# shadower.net
KiCad netlist of a schematic drawn in EAGLE
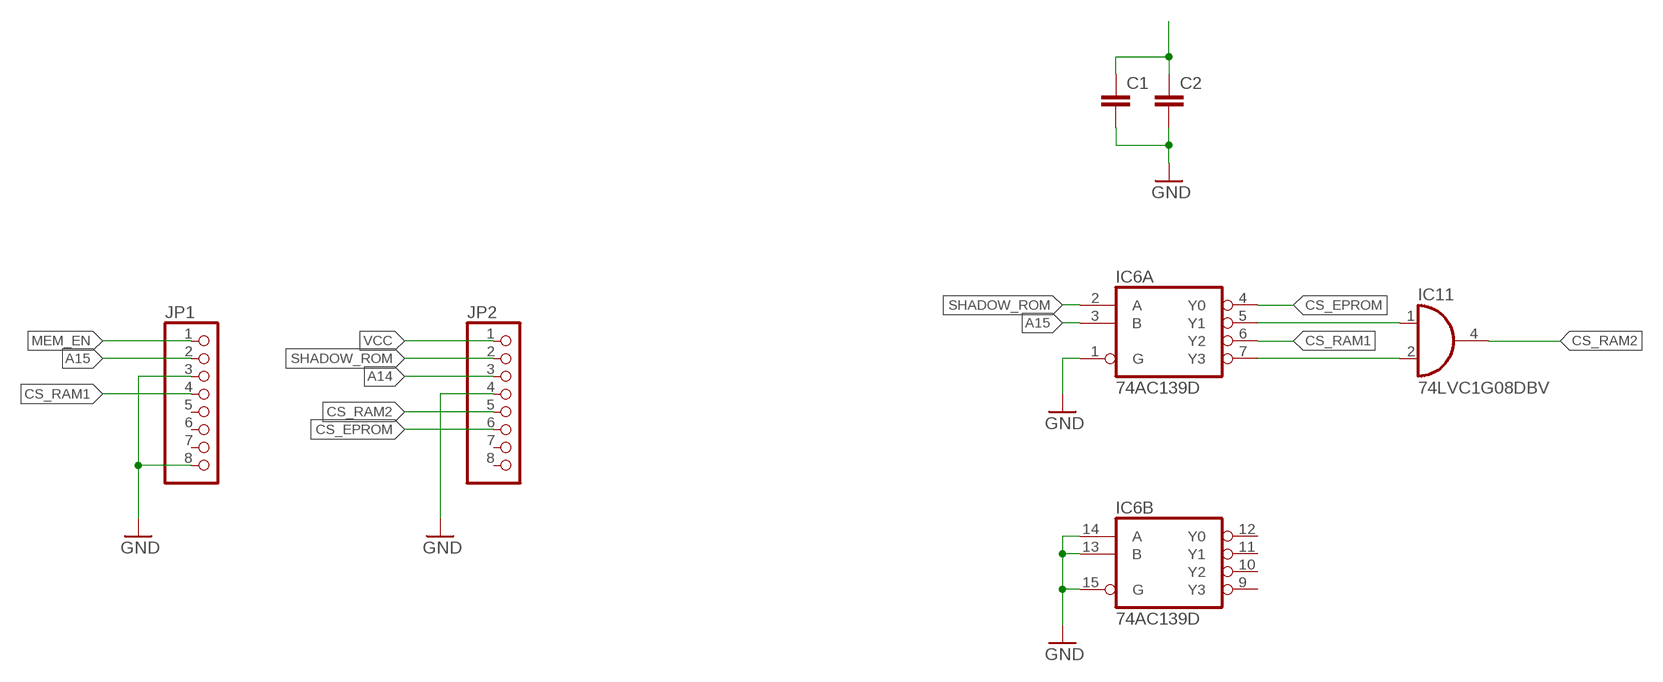
[diagram p0: schematic, sheet 1]

(export (version "E")
  (design (tool "Eeschema 10.0.6"))
  (components
    (comp (ref "C1")
      (value "C-EUC0603")
      (footprint "eagle-import:C0603")
      (libsource (lib "eagle-import") (part "C-EUC0603"))
    )
    (comp (ref "C2")
      (value "C-EUC0603")
      (footprint "eagle-import:C0603")
      (libsource (lib "eagle-import") (part "C-EUC0603"))
    )
    (comp (ref "IC6")
      (value "74AC139D")
      (footprint "eagle-import:SO16")
      (libsource (lib "eagle-import") (part "74139DAC"))
    )
    (comp (ref "IC11")
      (value "74LVC1G08DBV")
      (footprint "eagle-import:SOT23-5")
      (libsource (lib "eagle-import") (part "741G08DBVLVC"))
    )
    (comp (ref "JP1")
      (value "PINHD-1X8")
      (footprint "eagle-import:1X08")
      (libsource (lib "eagle-import") (part "PINHD-1X8"))
    )
    (comp (ref "JP2")
      (value "PINHD-1X8")
      (footprint "eagle-import:1X08")
      (libsource (lib "eagle-import") (part "PINHD-1X8"))
    )
  )
  (nets
    (net (code "1") (name "A14") (class "Default")
      (node (ref "JP2") (pin "3") (pinfunction "3_3") (pintype "passive"))
    )
    (net (code "2") (name "A15") (class "Default")
      (node (ref "IC6") (pin "3") (pinfunction "B_3") (pintype "input"))
      (node (ref "JP1") (pin "2") (pinfunction "2_2") (pintype "passive"))
    )
    (net (code "3") (name "CS_EPROM") (class "Default")
      (node (ref "IC6") (pin "4") (pinfunction "Y0_4") (pintype "output"))
      (node (ref "JP2") (pin "6") (pinfunction "6_6") (pintype "passive"))
    )
    (net (code "4") (name "CS_RAM1") (class "Default")
      (node (ref "IC6") (pin "6") (pinfunction "Y2_6") (pintype "output"))
      (node (ref "JP1") (pin "4") (pinfunction "4_4") (pintype "passive"))
    )
    (net (code "5") (name "CS_RAM2") (class "Default")
      (node (ref "IC11") (pin "4") (pinfunction "O_4") (pintype "output"))
      (node (ref "JP2") (pin "5") (pinfunction "5_5") (pintype "passive"))
    )
    (net (code "6") (name "GND") (class "Default")
      (node (ref "C1") (pin "2") (pinfunction "2_2") (pintype "passive"))
      (node (ref "C2") (pin "2") (pinfunction "2_2") (pintype "passive"))
      (node (ref "IC6") (pin "1") (pinfunction "G_1") (pintype "input"))
      (node (ref "IC6") (pin "13") (pinfunction "B_13") (pintype "input"))
      (node (ref "IC6") (pin "14") (pinfunction "A_14") (pintype "input"))
      (node (ref "IC6") (pin "15") (pinfunction "G_15") (pintype "input"))
      (node (ref "JP1") (pin "3") (pinfunction "3_3") (pintype "passive"))
      (node (ref "JP1") (pin "8") (pinfunction "8_8") (pintype "passive"))
      (node (ref "JP2") (pin "4") (pinfunction "4_4") (pintype "passive"))
    )
    (net (code "7") (name "MEM_EN") (class "Default")
      (node (ref "JP1") (pin "1") (pinfunction "1_1") (pintype "passive"))
    )
    (net (code "8") (name "Net-(IC11A-I0)") (class "Default")
      (node (ref "IC11") (pin "1") (pinfunction "I0_1") (pintype "input"))
      (node (ref "IC6") (pin "5") (pinfunction "Y1_5") (pintype "output"))
    )
    (net (code "9") (name "Net-(IC11A-I1)") (class "Default")
      (node (ref "IC11") (pin "2") (pinfunction "I1_2") (pintype "input"))
      (node (ref "IC6") (pin "7") (pinfunction "Y3_7") (pintype "output"))
    )
    (net (code "10") (name "SHADOW_ROM") (class "Default")
      (node (ref "IC6") (pin "2") (pinfunction "A_2") (pintype "input"))
      (node (ref "JP2") (pin "2") (pinfunction "2_2") (pintype "passive"))
    )
    (net (code "11") (name "VCC") (class "Default")
      (node (ref "C1") (pin "1") (pinfunction "1_1") (pintype "passive"))
      (node (ref "C2") (pin "1") (pinfunction "1_1") (pintype "passive"))
      (node (ref "JP2") (pin "1") (pinfunction "1_1") (pintype "passive"))
    )
    (net (code "12") (name "unconnected-(IC6B-Y0-Pad12)") (class "Default")
      (node (ref "IC6") (pin "12") (pinfunction "Y0_12") (pintype "output"))
    )
    (net (code "13") (name "unconnected-(IC6B-Y1-Pad11)") (class "Default")
      (node (ref "IC6") (pin "11") (pinfunction "Y1_11") (pintype "output"))
    )
    (net (code "14") (name "unconnected-(IC6B-Y2-Pad10)") (class "Default")
      (node (ref "IC6") (pin "10") (pinfunction "Y2_10") (pintype "output"))
    )
    (net (code "15") (name "unconnected-(IC6B-Y3-Pad9)") (class "Default")
      (node (ref "IC6") (pin "9") (pinfunction "Y3_9") (pintype "output"))
    )
    (net (code "16") (name "unconnected-(JP1-Pad5)") (class "Default")
      (node (ref "JP1") (pin "5") (pinfunction "5_5") (pintype "passive"))
    )
    (net (code "17") (name "unconnected-(JP1-Pad6)") (class "Default")
      (node (ref "JP1") (pin "6") (pinfunction "6_6") (pintype "passive"))
    )
    (net (code "18") (name "unconnected-(JP1-Pad7)") (class "Default")
      (node (ref "JP1") (pin "7") (pinfunction "7_7") (pintype "passive"))
    )
    (net (code "19") (name "unconnected-(JP2-Pad7)") (class "Default")
      (node (ref "JP2") (pin "7") (pinfunction "7_7") (pintype "passive"))
    )
    (net (code "20") (name "unconnected-(JP2-Pad8)") (class "Default")
      (node (ref "JP2") (pin "8") (pinfunction "8_8") (pintype "passive"))
    )
  )
)
